# Screen.net
KiCad netlist of a schematic drawn in Altium Designer
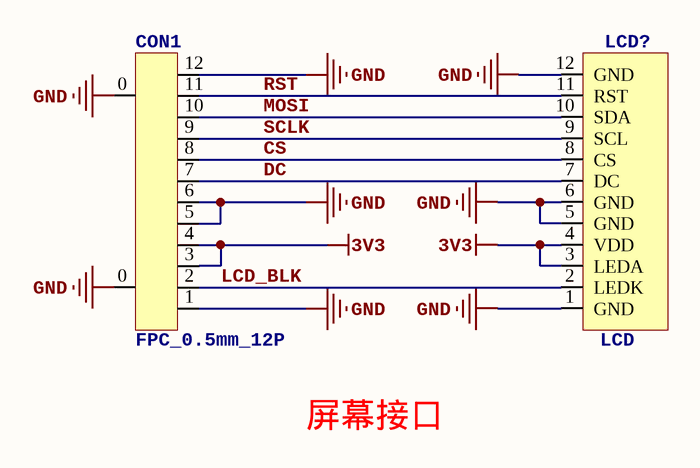
[diagram p0: Screen.SchDoc]

(export (version "E")
  (design (tool "Eeschema 10.0.6"))
  (components
    (comp (ref "CON1")
      (value "FPC_0.5mm_12P")
      (description "FPC连接器")
      (libsource (lib "SuperKnob") (part "FPC_0.5mm_12P"))
    )
    (comp (ref "LCD") (value "LCD?") (description "屏幕排线接口") (libsource (lib "Screen") (part "LCD")))
  )
  (nets
    (net (code "1") (name "/CS") (class "Default")
      (node (ref "CON1") (pin "8") (pinfunction "8_8") (pintype "passive"))
      (node (ref "LCD") (pin "8") (pinfunction "CS_8") (pintype "passive"))
    )
    (net (code "2") (name "/DC") (class "Default")
      (node (ref "CON1") (pin "7") (pinfunction "7_7") (pintype "passive"))
      (node (ref "LCD") (pin "7") (pinfunction "DC_7") (pintype "passive"))
    )
    (net (code "3") (name "/LCD_BLK") (class "Default")
      (node (ref "CON1") (pin "2") (pinfunction "2_2") (pintype "passive"))
      (node (ref "LCD") (pin "2") (pinfunction "LEDK_2") (pintype "passive"))
    )
    (net (code "4") (name "/MOSI") (class "Default")
      (node (ref "CON1") (pin "10") (pinfunction "10_10") (pintype "passive"))
      (node (ref "LCD") (pin "10") (pinfunction "SDA_10") (pintype "passive"))
    )
    (net (code "5") (name "/RST") (class "Default")
      (node (ref "CON1") (pin "11") (pinfunction "11_11") (pintype "passive"))
      (node (ref "LCD") (pin "11") (pinfunction "RST_11") (pintype "passive"))
    )
    (net (code "6") (name "/SCLK") (class "Default")
      (node (ref "CON1") (pin "9") (pinfunction "9_9") (pintype "passive"))
      (node (ref "LCD") (pin "9") (pinfunction "SCL_9") (pintype "passive"))
    )
    (net (code "7") (name "3V3") (class "Default")
      (node (ref "CON1") (pin "3") (pinfunction "3_3") (pintype "passive"))
      (node (ref "CON1") (pin "4") (pinfunction "4_4") (pintype "passive"))
      (node (ref "LCD") (pin "3") (pinfunction "LEDA_3") (pintype "passive"))
      (node (ref "LCD") (pin "4") (pinfunction "VDD_4") (pintype "passive"))
    )
    (net (code "8") (name "GND") (class "Default")
      (node (ref "CON1") (pin "0") (pinfunction "0_0") (pintype "passive"))
      (node (ref "CON1") (pin "1") (pinfunction "1_1") (pintype "passive"))
      (node (ref "CON1") (pin "12") (pinfunction "12_12") (pintype "passive"))
      (node (ref "CON1") (pin "5") (pinfunction "5_5") (pintype "passive"))
      (node (ref "CON1") (pin "6") (pinfunction "6_6") (pintype "passive"))
      (node (ref "LCD") (pin "1") (pinfunction "GND_1") (pintype "passive"))
      (node (ref "LCD") (pin "12") (pinfunction "GND_12") (pintype "passive"))
      (node (ref "LCD") (pin "5") (pinfunction "GND_5") (pintype "passive"))
      (node (ref "LCD") (pin "6") (pinfunction "GND_6") (pintype "passive"))
    )
  )
)
